# C.net
KiCad netlist of a schematic drawn in EAGLE
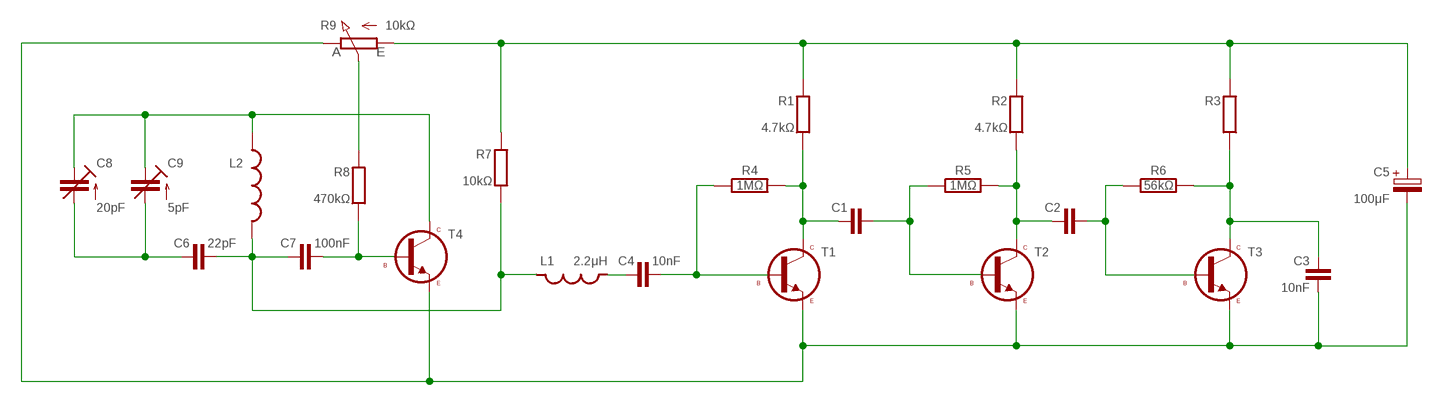
[diagram p0: schematic, sheet 1]

(export (version "E")
  (design (tool "Eeschema 10.0.6"))
  (components
    (comp (ref "C1")
      (value "C-H050-020X044")
      (footprint "eagle-import:C050-020X044")
      (libsource (lib "eagle-import") (part "C-H050-020X044"))
    )
    (comp (ref "C2")
      (value "C-H050-020X044")
      (footprint "eagle-import:C050-020X044")
      (libsource (lib "eagle-import") (part "C-H050-020X044"))
    )
    (comp (ref "C3")
      (value "10nF")
      (footprint "eagle-import:C050-025X060")
      (libsource (lib "eagle-import") (part "C025-025X060"))
    )
    (comp (ref "C4")
      (value "10nF")
      (footprint "eagle-import:C050-020X044")
      (libsource (lib "eagle-import") (part "C-H050-020X044"))
    )
    (comp (ref "C5")
      (value "100μF")
      (footprint "eagle-import:E2.5-4_V")
      (libsource (lib "eagle-import") (part "CPOLE2,5-4/V"))
    )
    (comp (ref "C6")
      (value "22pF")
      (footprint "eagle-import:C050-020X036")
      (libsource (lib "eagle-import") (part "C-H050-020X036"))
    )
    (comp (ref "C7")
      (value "100nF")
      (footprint "eagle-import:C075-020X044")
      (libsource (lib "eagle-import") (part "C-H075-020X044"))
    )
    (comp (ref "C8")
      (value "20pF")
      (footprint "eagle-import:TRIM-2222-808")
      (libsource (lib "eagle-import") (part "C-TR-PH201272222-808-2PIN"))
    )
    (comp (ref "C9")
      (value "5pF")
      (footprint "eagle-import:CTRIMTZ03")
      (libsource (lib "eagle-import") (part "C-TR-PH20127-TZ03"))
    )
    (comp (ref "L1")
      (value "2.2μH")
      (footprint "eagle-import:L-03_10")
      (libsource (lib "eagle-import") (part "L-H-SHORT-03/10"))
    )
    (comp (ref "L2")
      (value "L04/7")
      (footprint "eagle-import:L-04_8V")
      (libsource (lib "eagle-import") (part "L04/7"))
    )
    (comp (ref "R1")
      (value "4.7kΩ")
      (footprint "eagle-import:0204_10-V")
      (libsource (lib "eagle-import") (part "R0204/10-V"))
    )
    (comp (ref "R2")
      (value "4.7kΩ")
      (footprint "eagle-import:0204_10-V")
      (libsource (lib "eagle-import") (part "R0204/10-V"))
    )
    (comp (ref "R3")
      (value "R0204/10-V")
      (footprint "eagle-import:0204_10-V")
      (libsource (lib "eagle-import") (part "R0204/10-V"))
    )
    (comp (ref "R4")
      (value "1MΩ")
      (footprint "eagle-import:0204_7")
      (libsource (lib "eagle-import") (part "R-H0204/7"))
    )
    (comp (ref "R5")
      (value "1MΩ")
      (footprint "eagle-import:0204_7")
      (libsource (lib "eagle-import") (part "R-H0204/7"))
    )
    (comp (ref "R6")
      (value "56kΩ")
      (footprint "eagle-import:0204_7")
      (libsource (lib "eagle-import") (part "R-H0204/7"))
    )
    (comp (ref "R7")
      (value "10kΩ")
      (footprint "eagle-import:0204_10-V")
      (libsource (lib "eagle-import") (part "R0204/10-V"))
    )
    (comp (ref "R8")
      (value "470kΩ")
      (footprint "eagle-import:0204_10-V")
      (libsource (lib "eagle-import") (part "R0204/10-V"))
    )
    (comp (ref "R9")
      (value "10kΩ")
      (footprint "eagle-import:POT")
      (libsource (lib "eagle-import") (part "POT-H"))
    )
    (comp (ref "T1")
      (value "BC547-A")
      (footprint "eagle-import:TO92-CBE-A")
      (libsource (lib "eagle-import") (part "BC547-A"))
    )
    (comp (ref "T2")
      (value "BC547-A")
      (footprint "eagle-import:TO92-CBE-A")
      (libsource (lib "eagle-import") (part "BC547-A"))
    )
    (comp (ref "T3")
      (value "BC547-A")
      (footprint "eagle-import:TO92-CBE-A")
      (libsource (lib "eagle-import") (part "BC547-A"))
    )
    (comp (ref "T4")
      (value "BC547-A")
      (footprint "eagle-import:TO92-CBE-A")
      (libsource (lib "eagle-import") (part "BC547-A"))
    )
  )
  (nets
    (net (code "1") (name "Net-(C4-Pad1)") (class "Default")
      (node (ref "C4") (pin "1") (pinfunction "1_1") (pintype "passive"))
      (node (ref "L1") (pin "1") (pinfunction "1_1") (pintype "passive"))
    )
    (net (code "2") (name "Net-(C8-A)") (class "Default")
      (node (ref "C6") (pin "1") (pinfunction "1_1") (pintype "passive"))
      (node (ref "C8") (pin "1") (pinfunction "A_1") (pintype "passive"))
      (node (ref "C9") (pin "1") (pinfunction "A_1") (pintype "passive"))
    )
    (net (code "3") (name "Net-(C8-E)") (class "Default")
      (node (ref "C8") (pin "2") (pinfunction "E_2") (pintype "passive"))
      (node (ref "C9") (pin "2") (pinfunction "E_2") (pintype "passive"))
      (node (ref "L2") (pin "2") (pinfunction "1_2") (pintype "passive"))
      (node (ref "T4") (pin "1") (pinfunction "C_1") (pintype "passive"))
    )
    (net (code "4") (name "Net-(L2-2)") (class "Default")
      (node (ref "C6") (pin "2") (pinfunction "2_2") (pintype "passive"))
      (node (ref "C7") (pin "1") (pinfunction "1_1") (pintype "passive"))
      (node (ref "L1") (pin "2") (pinfunction "2_2") (pintype "passive"))
      (node (ref "L2") (pin "1") (pinfunction "2_1") (pintype "passive"))
      (node (ref "R7") (pin "2") (pinfunction "1_2") (pintype "passive"))
    )
    (net (code "5") (name "Net-(R1-1)") (class "Default")
      (node (ref "C1") (pin "1") (pinfunction "1_1") (pintype "passive"))
      (node (ref "R1") (pin "2") (pinfunction "1_2") (pintype "passive"))
      (node (ref "R4") (pin "2") (pinfunction "2_2") (pintype "passive"))
      (node (ref "T1") (pin "1") (pinfunction "C_1") (pintype "passive"))
    )
    (net (code "6") (name "Net-(R1-2)") (class "Default")
      (node (ref "C5") (pin "+") (pinfunction "+_+") (pintype "passive"))
      (node (ref "R1") (pin "1") (pinfunction "2_1") (pintype "passive"))
      (node (ref "R2") (pin "1") (pinfunction "2_1") (pintype "passive"))
      (node (ref "R3") (pin "1") (pinfunction "2_1") (pintype "passive"))
      (node (ref "R7") (pin "1") (pinfunction "2_1") (pintype "passive"))
      (node (ref "R9") (pin "A") (pinfunction "A_A") (pintype "passive"))
    )
    (net (code "7") (name "Net-(R2-1)") (class "Default")
      (node (ref "C2") (pin "1") (pinfunction "1_1") (pintype "passive"))
      (node (ref "R2") (pin "2") (pinfunction "1_2") (pintype "passive"))
      (node (ref "R5") (pin "2") (pinfunction "2_2") (pintype "passive"))
      (node (ref "T2") (pin "1") (pinfunction "C_1") (pintype "passive"))
    )
    (net (code "8") (name "Net-(R3-1)") (class "Default")
      (node (ref "C3") (pin "1") (pinfunction "1_1") (pintype "passive"))
      (node (ref "R3") (pin "2") (pinfunction "1_2") (pintype "passive"))
      (node (ref "R6") (pin "2") (pinfunction "2_2") (pintype "passive"))
      (node (ref "T3") (pin "1") (pinfunction "C_1") (pintype "passive"))
    )
    (net (code "9") (name "Net-(R8-1)") (class "Default")
      (node (ref "C7") (pin "2") (pinfunction "2_2") (pintype "passive"))
      (node (ref "R8") (pin "2") (pinfunction "1_2") (pintype "passive"))
      (node (ref "T4") (pin "2") (pinfunction "B_2") (pintype "passive"))
    )
    (net (code "10") (name "Net-(R8-2)") (class "Default")
      (node (ref "R8") (pin "1") (pinfunction "2_1") (pintype "passive"))
      (node (ref "R9") (pin "S") (pinfunction "S_S") (pintype "passive"))
    )
    (net (code "11") (name "Net-(T1-B)") (class "Default")
      (node (ref "C4") (pin "2") (pinfunction "2_2") (pintype "passive"))
      (node (ref "R4") (pin "1") (pinfunction "1_1") (pintype "passive"))
      (node (ref "T1") (pin "2") (pinfunction "B_2") (pintype "passive"))
    )
    (net (code "12") (name "Net-(T1-E)") (class "Default")
      (node (ref "C3") (pin "2") (pinfunction "2_2") (pintype "passive"))
      (node (ref "C5") (pin "-") (pinfunction "-_-") (pintype "passive"))
      (node (ref "R9") (pin "E") (pinfunction "E_E") (pintype "passive"))
      (node (ref "T1") (pin "3") (pinfunction "E_3") (pintype "passive"))
      (node (ref "T2") (pin "3") (pinfunction "E_3") (pintype "passive"))
      (node (ref "T3") (pin "3") (pinfunction "E_3") (pintype "passive"))
      (node (ref "T4") (pin "3") (pinfunction "E_3") (pintype "passive"))
    )
    (net (code "13") (name "Net-(T2-B)") (class "Default")
      (node (ref "C1") (pin "2") (pinfunction "2_2") (pintype "passive"))
      (node (ref "R5") (pin "1") (pinfunction "1_1") (pintype "passive"))
      (node (ref "T2") (pin "2") (pinfunction "B_2") (pintype "passive"))
    )
    (net (code "14") (name "Net-(T3-B)") (class "Default")
      (node (ref "C2") (pin "2") (pinfunction "2_2") (pintype "passive"))
      (node (ref "R6") (pin "1") (pinfunction "1_1") (pintype "passive"))
      (node (ref "T3") (pin "2") (pinfunction "B_2") (pintype "passive"))
    )
  )
)
